# adapter.net
KiCad netlist of a schematic drawn in EAGLE
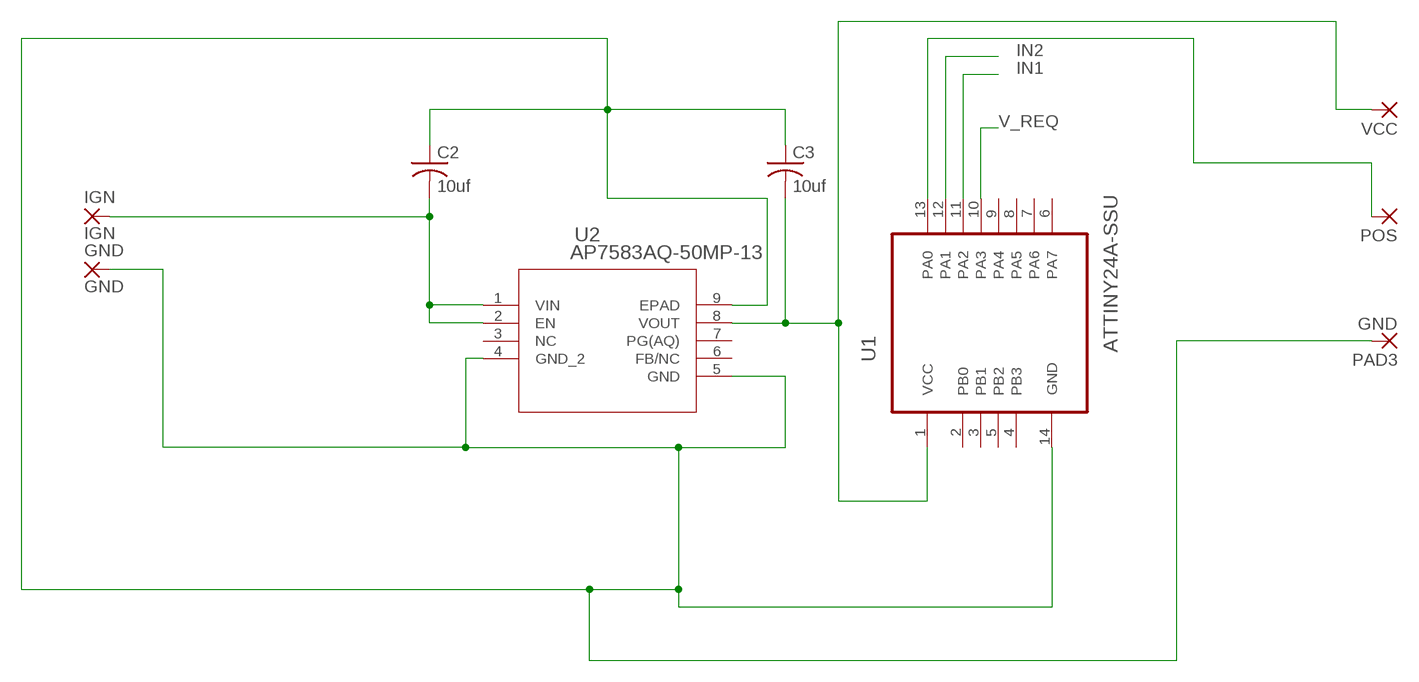
[diagram p0: schematic, sheet 1]
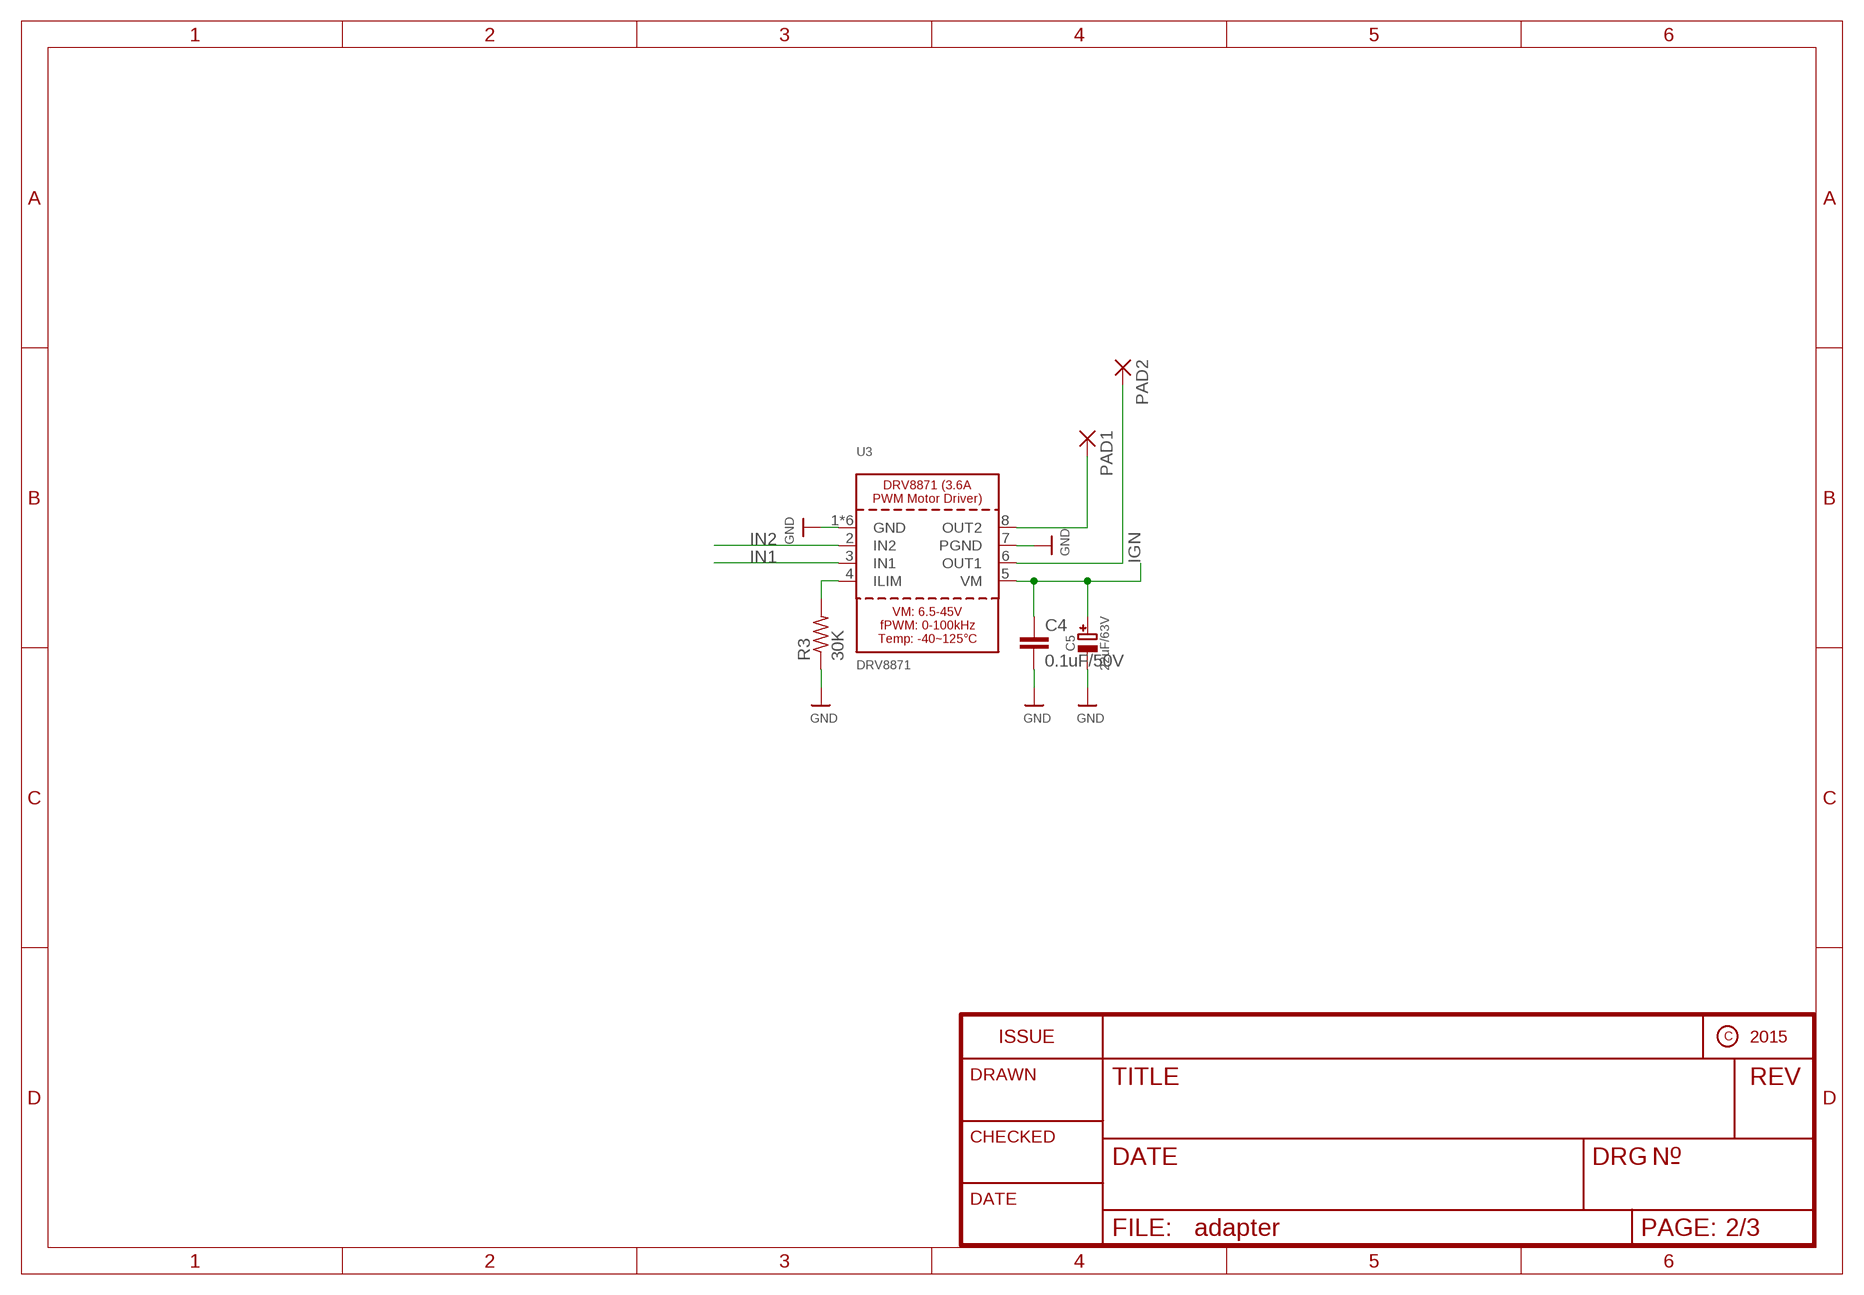
[diagram p1: schematic, sheet 2]
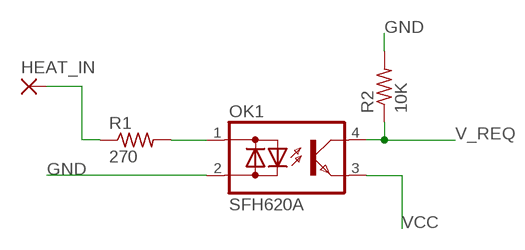
[diagram p2: schematic, sheet 3]

(export (version "E")
  (design (tool "Eeschema 10.0.6"))
  (components
    (comp (ref "C2")
      (value "10uf")
      (footprint "eagle-import:C1206")
      (libsource (lib "eagle-import") (part "C-USC1206"))
    )
    (comp (ref "C3")
      (value "10uf")
      (footprint "eagle-import:C1206")
      (libsource (lib "eagle-import") (part "C-USC1206"))
    )
    (comp (ref "GND")
      (value "GND")
      (footprint "eagle-import:2,15_1,0")
      (libsource (lib "eagle-import") (part "2,15/1,0"))
    )
    (comp (ref "IGN")
      (value "IGN")
      (footprint "eagle-import:2,15_1,0")
      (libsource (lib "eagle-import") (part "2,15/1,0"))
    )
    (comp (ref "PAD3")
      (value "GND")
      (footprint "eagle-import:2,15_1,0")
      (libsource (lib "eagle-import") (part "2,15/1,0"))
    )
    (comp (ref "POS")
      (value "2,15/1,0")
      (footprint "eagle-import:2,15_1,0")
      (libsource (lib "eagle-import") (part "2,15/1,0"))
    )
    (comp (ref "U1")
      (value "ATTINY24A-SSU")
      (footprint "eagle-import:SOIC127P600X175-14N")
      (libsource (lib "eagle-import") (part "ATTINY24A-SSU"))
    )
    (comp (ref "U2")
      (value "AP7583AQ-50MP-13")
      (footprint "eagle-import:MSOP-8EP_DIO")
      (fields (field (name "COPYRIGHT") "Copyright (C) 2024 Ultra Librarian. All rights reserved."))
      (libsource (lib "eagle-import") (part "AP7583AQ-50MP-13"))
    )
    (comp (ref "VCC")
      (value "2,15/1,0")
      (footprint "eagle-import:2,15_1,0")
      (libsource (lib "eagle-import") (part "2,15/1,0"))
    )
    (comp (ref "C4")
      (value "0.1uF/50V")
      (footprint "eagle-import:C1206")
      (libsource (lib "eagle-import") (part "C-EUC1206"))
    )
    (comp (ref "C5")
      (value "22uF/63V")
      (footprint "eagle-import:PANASONIC_D")
      (libsource (lib "eagle-import") (part "CAP_ELECTROLYTICPANASONIC_D"))
    )
    (comp (ref "PAD1")
      (value "2,15/1,0")
      (footprint "eagle-import:2,15_1,0")
      (libsource (lib "eagle-import") (part "2,15/1,0"))
    )
    (comp (ref "PAD2")
      (value "2,15/1,0")
      (footprint "eagle-import:2,15_1,0")
      (libsource (lib "eagle-import") (part "2,15/1,0"))
    )
    (comp (ref "R3")
      (value "30K")
      (footprint "eagle-import:M1206")
      (libsource (lib "eagle-import") (part "R-US_M1206"))
    )
    (comp (ref "U3")
      (value "DRV8871")
      (footprint "eagle-import:HSOP8")
      (libsource (lib "eagle-import") (part "DRV8871"))
    )
    (comp (ref "HEAT_IN")
      (value "2,15/1,0")
      (footprint "eagle-import:2,15_1,0")
      (libsource (lib "eagle-import") (part "2,15/1,0"))
    )
    (comp (ref "OK1")
      (value "SFH620A")
      (footprint "eagle-import:DIL04")
      (fields (field (name "MPN") "SFH620A-2"))
      (libsource (lib "eagle-import") (part "SFH620A"))
    )
    (comp (ref "R1")
      (value "270")
      (footprint "eagle-import:R2010")
      (libsource (lib "eagle-import") (part "R-US_R2010"))
    )
    (comp (ref "R2")
      (value "10K")
      (footprint "eagle-import:M1206")
      (libsource (lib "eagle-import") (part "R-US_M1206"))
    )
  )
  (nets
    (net (code "1") (name "GND") (class "Default")
      (node (ref "C2") (pin "1") (pinfunction "1_1") (pintype "passive"))
      (node (ref "C3") (pin "1") (pinfunction "1_1") (pintype "passive"))
      (node (ref "C4") (pin "2") (pinfunction "2_2") (pintype "passive"))
      (node (ref "C5") (pin "-") (pinfunction "-_-") (pintype "passive"))
      (node (ref "GND") (pin "1") (pinfunction "P_1") (pintype "passive"))
      (node (ref "OK1") (pin "2") (pinfunction "AC2_2") (pintype "passive"))
      (node (ref "PAD3") (pin "1") (pinfunction "P_1") (pintype "passive"))
      (node (ref "R2") (pin "2") (pinfunction "2_2") (pintype "passive"))
      (node (ref "R3") (pin "1") (pinfunction "1_1") (pintype "passive"))
      (node (ref "U1") (pin "14") (pinfunction "GND_14") (pintype "power_in"))
      (node (ref "U2") (pin "4") (pinfunction "GND_2_4") (pintype "passive"))
      (node (ref "U2") (pin "5") (pinfunction "GND_5") (pintype "passive"))
      (node (ref "U2") (pin "9") (pinfunction "EPAD_9") (pintype "passive"))
      (node (ref "U3") (pin "1") (pinfunction "GND_1") (pintype "power_in"))
      (node (ref "U3") (pin "7") (pinfunction "PGND_7") (pintype "power_in"))
      (node (ref "U3") (pin "GND") (pinfunction "GND_GND") (pintype "power_in"))
      (node (ref "U3") (pin "P$1") (pinfunction "GND_P$1") (pintype "power_in"))
      (node (ref "U3") (pin "P$2") (pinfunction "GND_P$2") (pintype "power_in"))
      (node (ref "U3") (pin "P$3") (pinfunction "GND_P$3") (pintype "power_in"))
      (node (ref "U3") (pin "P$4") (pinfunction "GND_P$4") (pintype "power_in"))
    )
    (net (code "2") (name "IGN") (class "Default")
      (node (ref "C2") (pin "2") (pinfunction "2_2") (pintype "passive"))
      (node (ref "C4") (pin "1") (pinfunction "1_1") (pintype "passive"))
      (node (ref "C5") (pin "+") (pinfunction "+_+") (pintype "passive"))
      (node (ref "IGN") (pin "1") (pinfunction "P_1") (pintype "passive"))
      (node (ref "U2") (pin "1") (pinfunction "VIN_1") (pintype "input"))
      (node (ref "U2") (pin "2") (pinfunction "EN_2") (pintype "input"))
      (node (ref "U3") (pin "5") (pinfunction "VM_5") (pintype "power_in"))
    )
    (net (code "3") (name "IN1") (class "Default")
      (node (ref "U1") (pin "11") (pinfunction "PA2_11") (pintype "bidirectional"))
      (node (ref "U3") (pin "3") (pinfunction "IN1_3") (pintype "input"))
    )
    (net (code "4") (name "IN2") (class "Default")
      (node (ref "U1") (pin "12") (pinfunction "PA1_12") (pintype "bidirectional"))
      (node (ref "U3") (pin "2") (pinfunction "IN2_2") (pintype "input"))
    )
    (net (code "5") (name "Net-(HEAT_IN-P)") (class "Default")
      (node (ref "HEAT_IN") (pin "1") (pinfunction "P_1") (pintype "passive"))
      (node (ref "R1") (pin "1") (pinfunction "1_1") (pintype "passive"))
    )
    (net (code "6") (name "Net-(OK1-AC1)") (class "Default")
      (node (ref "OK1") (pin "1") (pinfunction "AC1_1") (pintype "passive"))
      (node (ref "R1") (pin "2") (pinfunction "2_2") (pintype "passive"))
    )
    (net (code "7") (name "Net-(PAD1-P)") (class "Default")
      (node (ref "PAD1") (pin "1") (pinfunction "P_1") (pintype "passive"))
      (node (ref "U3") (pin "8") (pinfunction "OUT2_8") (pintype "output"))
    )
    (net (code "8") (name "Net-(PAD2-P)") (class "Default")
      (node (ref "PAD2") (pin "1") (pinfunction "P_1") (pintype "passive"))
      (node (ref "U3") (pin "6") (pinfunction "OUT1_6") (pintype "output"))
    )
    (net (code "9") (name "Net-(POS-P)") (class "Default")
      (node (ref "POS") (pin "1") (pinfunction "P_1") (pintype "passive"))
      (node (ref "U1") (pin "13") (pinfunction "PA0_13") (pintype "bidirectional"))
    )
    (net (code "10") (name "Net-(U3-ILIM)") (class "Default")
      (node (ref "R3") (pin "2") (pinfunction "2_2") (pintype "passive"))
      (node (ref "U3") (pin "4") (pinfunction "ILIM_4") (pintype "input"))
    )
    (net (code "11") (name "VCC") (class "Default")
      (node (ref "C3") (pin "2") (pinfunction "2_2") (pintype "passive"))
      (node (ref "OK1") (pin "3") (pinfunction "E_3") (pintype "passive"))
      (node (ref "U1") (pin "1") (pinfunction "VCC_1") (pintype "power_in"))
      (node (ref "U2") (pin "8") (pinfunction "VOUT_8") (pintype "output"))
      (node (ref "VCC") (pin "1") (pinfunction "P_1") (pintype "passive"))
    )
    (net (code "12") (name "V_REQ") (class "Default")
      (node (ref "OK1") (pin "4") (pinfunction "C_4") (pintype "passive"))
      (node (ref "R2") (pin "1") (pinfunction "1_1") (pintype "passive"))
      (node (ref "U1") (pin "10") (pinfunction "PA3_10") (pintype "bidirectional"))
    )
    (net (code "13") (name "unconnected-(U1-PA4-Pad9)") (class "Default")
      (node (ref "U1") (pin "9") (pinfunction "PA4_9") (pintype "bidirectional"))
    )
    (net (code "14") (name "unconnected-(U1-PA5-Pad8)") (class "Default")
      (node (ref "U1") (pin "8") (pinfunction "PA5_8") (pintype "bidirectional"))
    )
    (net (code "15") (name "unconnected-(U1-PA6-Pad7)") (class "Default")
      (node (ref "U1") (pin "7") (pinfunction "PA6_7") (pintype "bidirectional"))
    )
    (net (code "16") (name "unconnected-(U1-PA7-Pad6)") (class "Default")
      (node (ref "U1") (pin "6") (pinfunction "PA7_6") (pintype "bidirectional"))
    )
    (net (code "17") (name "unconnected-(U1-PB0-Pad2)") (class "Default")
      (node (ref "U1") (pin "2") (pinfunction "PB0_2") (pintype "bidirectional"))
    )
    (net (code "18") (name "unconnected-(U1-PB1-Pad3)") (class "Default")
      (node (ref "U1") (pin "3") (pinfunction "PB1_3") (pintype "bidirectional"))
    )
    (net (code "19") (name "unconnected-(U1-PB2-Pad5)") (class "Default")
      (node (ref "U1") (pin "5") (pinfunction "PB2_5") (pintype "bidirectional"))
    )
    (net (code "20") (name "unconnected-(U1-PB3-Pad4)") (class "Default")
      (node (ref "U1") (pin "4") (pinfunction "PB3_4") (pintype "bidirectional"))
    )
    (net (code "21") (name "unconnected-(U2-FB{slash}NC-Pad6)") (class "Default")
      (node (ref "U2") (pin "6") (pinfunction "FB/NC_6") (pintype "passive"))
    )
    (net (code "22") (name "unconnected-(U2-NC-Pad3)") (class "Default")
      (node (ref "U2") (pin "3") (pinfunction "NC_3") (pintype "no_connect"))
    )
    (net (code "23") (name "unconnected-(U2-PG(AQ)-Pad7)") (class "Default")
      (node (ref "U2") (pin "7") (pinfunction "PG(AQ)_7") (pintype "passive"))
    )
  )
)
